# eRIC_BEE.net
KiCad netlist of a schematic drawn in EAGLE
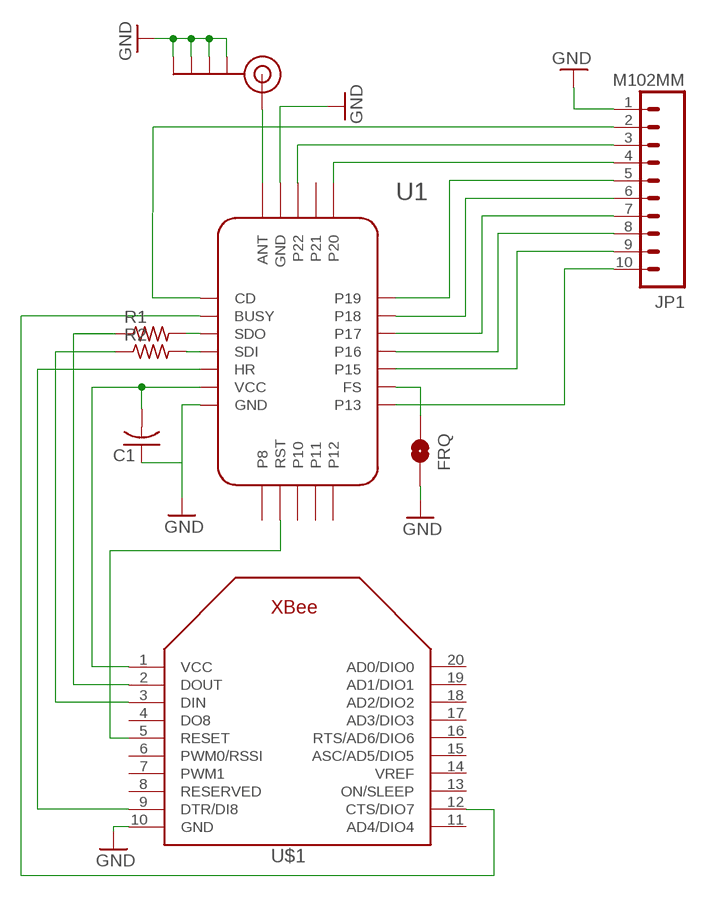
[diagram p0: schematic, sheet 1]

(export (version "E")
  (design (tool "Eeschema 10.0.6"))
  (components
    (comp (ref "C1")
      (value "C-USC0402")
      (footprint "eagle-import:C0402")
      (libsource (lib "eagle-import") (part "C-USC0402"))
    )
    (comp (ref "FRQ")
      (value "JUMPER-PAD-2-NOYES_SILK")
      (footprint "eagle-import:PAD-JUMPER-2-NO_YES_SILK")
      (libsource (lib "eagle-import") (part "JUMPER-PAD-2-NOYES_SILK"))
    )
    (comp (ref "J$2")
      (value "SMA_EDGE")
      (footprint "eagle-import:SMA-EDGE")
      (libsource (lib "eagle-import") (part "SMA_EDGE"))
    )
    (comp (ref "JP1")
      (value "M102MM")
      (footprint "eagle-import:1X10-2MM")
      (libsource (lib "eagle-import") (part "M102MM"))
    )
    (comp (ref "R1")
      (value "R-US_R0402")
      (footprint "eagle-import:R0402")
      (libsource (lib "eagle-import") (part "R-US_R0402"))
    )
    (comp (ref "R2")
      (value "R-US_R0402")
      (footprint "eagle-import:R0402")
      (libsource (lib "eagle-import") (part "R-US_R0402"))
    )
    (comp (ref "U$1")
      (value "XBEE")
      (footprint "eagle-import:XBEE")
      (libsource (lib "eagle-import") (part "XBEE"))
    )
    (comp (ref "U1")
      (value "ERIC")
      (footprint "eagle-import:ERIC")
      (libsource (lib "eagle-import") (part "ERIC"))
    )
  )
  (nets
    (net (code "1") (name "GND") (class "Default")
      (node (ref "C1") (pin "1") (pinfunction "1_1") (pintype "passive"))
      (node (ref "FRQ") (pin "2") (pinfunction "2_2") (pintype "passive"))
      (node (ref "J$2") (pin "GND@0") (pinfunction "GND_GND@0") (pintype "bidirectional"))
      (node (ref "J$2") (pin "GND@1") (pinfunction "GND_GND@1") (pintype "bidirectional"))
      (node (ref "J$2") (pin "GND@2") (pinfunction "GND_GND@2") (pintype "bidirectional"))
      (node (ref "J$2") (pin "GND@3") (pinfunction "GND_GND@3") (pintype "bidirectional"))
      (node (ref "JP1") (pin "1") (pinfunction "1_1") (pintype "passive"))
      (node (ref "U$1") (pin "10") (pinfunction "GND_10") (pintype "power_in"))
      (node (ref "U1") (pin "AGND") (pinfunction "GND_AGND") (pintype "bidirectional"))
      (node (ref "U1") (pin "GND") (pinfunction "GND_GND") (pintype "power_in"))
    )
    (net (code "2") (name "Net-(FRQ-Pad1)") (class "Default")
      (node (ref "FRQ") (pin "1") (pinfunction "1_1") (pintype "passive"))
      (node (ref "U1") (pin "FS") (pinfunction "FS_FS") (pintype "bidirectional"))
    )
    (net (code "3") (name "Net-(J$2-SIGNAL)") (class "Default")
      (node (ref "J$2") (pin "SIG") (pinfunction "SIGNAL_SIG") (pintype "bidirectional"))
      (node (ref "U1") (pin "ANT") (pinfunction "ANT_ANT") (pintype "bidirectional"))
    )
    (net (code "4") (name "Net-(JP1-Pad2)") (class "Default")
      (node (ref "JP1") (pin "2") (pinfunction "2_2") (pintype "passive"))
      (node (ref "U1") (pin "CD") (pinfunction "CD_CD") (pintype "bidirectional"))
    )
    (net (code "5") (name "Net-(R1-Pad2)") (class "Default")
      (node (ref "R1") (pin "2") (pinfunction "2_2") (pintype "passive"))
      (node (ref "U1") (pin "SDO") (pinfunction "SDO_SDO") (pintype "bidirectional"))
    )
    (net (code "6") (name "Net-(R2-Pad2)") (class "Default")
      (node (ref "R2") (pin "2") (pinfunction "2_2") (pintype "passive"))
      (node (ref "U1") (pin "SDI") (pinfunction "SDI_SDI") (pintype "bidirectional"))
    )
    (net (code "7") (name "Net-(U$1-CTS{slash}DIO7)") (class "Default")
      (node (ref "U$1") (pin "12") (pinfunction "CTS/DIO7_12") (pintype "bidirectional"))
      (node (ref "U1") (pin "BUSY") (pinfunction "BUSY_BUSY") (pintype "bidirectional"))
    )
    (net (code "8") (name "Net-(U$1-DIN)") (class "Default")
      (node (ref "R2") (pin "1") (pinfunction "1_1") (pintype "passive"))
      (node (ref "U$1") (pin "3") (pinfunction "DIN_3") (pintype "input"))
    )
    (net (code "9") (name "Net-(U$1-DOUT)") (class "Default")
      (node (ref "R1") (pin "1") (pinfunction "1_1") (pintype "passive"))
      (node (ref "U$1") (pin "2") (pinfunction "DOUT_2") (pintype "output"))
    )
    (net (code "10") (name "Net-(U$1-DTR{slash}DI8)") (class "Default")
      (node (ref "U$1") (pin "9") (pinfunction "DTR/DI8_9") (pintype "input"))
      (node (ref "U1") (pin "HR") (pinfunction "HR_HR") (pintype "bidirectional"))
    )
    (net (code "11") (name "Net-(U$1-RESET)") (class "Default")
      (node (ref "U$1") (pin "5") (pinfunction "RESET_5") (pintype "input"))
      (node (ref "U1") (pin "E9") (pinfunction "RST_E9") (pintype "bidirectional"))
    )
    (net (code "12") (name "Net-(U$1-VCC)") (class "Default")
      (node (ref "C1") (pin "2") (pinfunction "2_2") (pintype "passive"))
      (node (ref "U$1") (pin "1") (pinfunction "VCC_1") (pintype "power_in"))
      (node (ref "U1") (pin "VCC") (pinfunction "VCC_VCC") (pintype "power_in"))
    )
    (net (code "13") (name "Net-(U1-P13)") (class "Default")
      (node (ref "JP1") (pin "10") (pinfunction "10_10") (pintype "passive"))
      (node (ref "U1") (pin "E13") (pinfunction "P13_E13") (pintype "bidirectional"))
    )
    (net (code "14") (name "Net-(U1-P15)") (class "Default")
      (node (ref "JP1") (pin "9") (pinfunction "9_9") (pintype "passive"))
      (node (ref "U1") (pin "E15") (pinfunction "P15_E15") (pintype "bidirectional"))
    )
    (net (code "15") (name "Net-(U1-P16)") (class "Default")
      (node (ref "JP1") (pin "8") (pinfunction "8_8") (pintype "passive"))
      (node (ref "U1") (pin "E16") (pinfunction "P16_E16") (pintype "bidirectional"))
    )
    (net (code "16") (name "Net-(U1-P17)") (class "Default")
      (node (ref "JP1") (pin "7") (pinfunction "7_7") (pintype "passive"))
      (node (ref "U1") (pin "E17") (pinfunction "P17_E17") (pintype "bidirectional"))
    )
    (net (code "17") (name "Net-(U1-P18)") (class "Default")
      (node (ref "JP1") (pin "6") (pinfunction "6_6") (pintype "passive"))
      (node (ref "U1") (pin "E18") (pinfunction "P18_E18") (pintype "bidirectional"))
    )
    (net (code "18") (name "Net-(U1-P19)") (class "Default")
      (node (ref "JP1") (pin "5") (pinfunction "5_5") (pintype "passive"))
      (node (ref "U1") (pin "E19") (pinfunction "P19_E19") (pintype "bidirectional"))
    )
    (net (code "19") (name "Net-(U1-P20)") (class "Default")
      (node (ref "JP1") (pin "4") (pinfunction "4_4") (pintype "passive"))
      (node (ref "U1") (pin "E20") (pinfunction "P20_E20") (pintype "bidirectional"))
    )
    (net (code "20") (name "Net-(U1-P22)") (class "Default")
      (node (ref "JP1") (pin "3") (pinfunction "3_3") (pintype "passive"))
      (node (ref "U1") (pin "E22") (pinfunction "P22_E22") (pintype "bidirectional"))
    )
    (net (code "21") (name "unconnected-(U$1-AD0{slash}DIO0-Pad20)") (class "Default")
      (node (ref "U$1") (pin "20") (pinfunction "AD0/DIO0_20") (pintype "bidirectional"))
    )
    (net (code "22") (name "unconnected-(U$1-AD1{slash}DIO1-Pad19)") (class "Default")
      (node (ref "U$1") (pin "19") (pinfunction "AD1/DIO1_19") (pintype "bidirectional"))
    )
    (net (code "23") (name "unconnected-(U$1-AD2{slash}DIO2-Pad18)") (class "Default")
      (node (ref "U$1") (pin "18") (pinfunction "AD2/DIO2_18") (pintype "bidirectional"))
    )
    (net (code "24") (name "unconnected-(U$1-AD3{slash}DIO3-Pad17)") (class "Default")
      (node (ref "U$1") (pin "17") (pinfunction "AD3/DIO3_17") (pintype "bidirectional"))
    )
    (net (code "25") (name "unconnected-(U$1-AD4{slash}DIO4-Pad11)") (class "Default")
      (node (ref "U$1") (pin "11") (pinfunction "AD4/DIO4_11") (pintype "bidirectional"))
    )
    (net (code "26") (name "unconnected-(U$1-ASC{slash}AD5{slash}DIO5-Pad15)") (class "Default")
      (node (ref "U$1") (pin "15") (pinfunction "ASC/AD5/DIO5_15") (pintype "bidirectional"))
    )
    (net (code "27") (name "unconnected-(U$1-DO8-Pad4)") (class "Default")
      (node (ref "U$1") (pin "4") (pinfunction "DO8_4") (pintype "output"))
    )
    (net (code "28") (name "unconnected-(U$1-ON{slash}SLEEP-Pad13)") (class "Default")
      (node (ref "U$1") (pin "13") (pinfunction "ON/SLEEP_13") (pintype "output"))
    )
    (net (code "29") (name "unconnected-(U$1-PWM0{slash}RSSI-Pad6)") (class "Default")
      (node (ref "U$1") (pin "6") (pinfunction "PWM0/RSSI_6") (pintype "output"))
    )
    (net (code "30") (name "unconnected-(U$1-PWM1-Pad7)") (class "Default")
      (node (ref "U$1") (pin "7") (pinfunction "PWM1_7") (pintype "output"))
    )
    (net (code "31") (name "unconnected-(U$1-RESERVED-Pad8)") (class "Default")
      (node (ref "U$1") (pin "8") (pinfunction "RESERVED_8") (pintype "no_connect"))
    )
    (net (code "32") (name "unconnected-(U$1-RTS{slash}AD6{slash}DIO6-Pad16)") (class "Default")
      (node (ref "U$1") (pin "16") (pinfunction "RTS/AD6/DIO6_16") (pintype "bidirectional"))
    )
    (net (code "33") (name "unconnected-(U$1-VREF-Pad14)") (class "Default")
      (node (ref "U$1") (pin "14") (pinfunction "VREF_14") (pintype "input"))
    )
    (net (code "34") (name "unconnected-(U1-P8-PadE8)") (class "Default")
      (node (ref "U1") (pin "E8") (pinfunction "P8_E8") (pintype "bidirectional"))
    )
    (net (code "35") (name "unconnected-(U1-P10-PadE10)") (class "Default")
      (node (ref "U1") (pin "E10") (pinfunction "P10_E10") (pintype "bidirectional"))
    )
    (net (code "36") (name "unconnected-(U1-P11-PadE11)") (class "Default")
      (node (ref "U1") (pin "E11") (pinfunction "P11_E11") (pintype "bidirectional"))
    )
    (net (code "37") (name "unconnected-(U1-P12-PadE12)") (class "Default")
      (node (ref "U1") (pin "E12") (pinfunction "P12_E12") (pintype "bidirectional"))
    )
    (net (code "38") (name "unconnected-(U1-P21-PadE21)") (class "Default")
      (node (ref "U1") (pin "E21") (pinfunction "P21_E21") (pintype "bidirectional"))
    )
  )
)
